# bat_connectors.net
KiCad netlist of a schematic drawn in Altium Designer
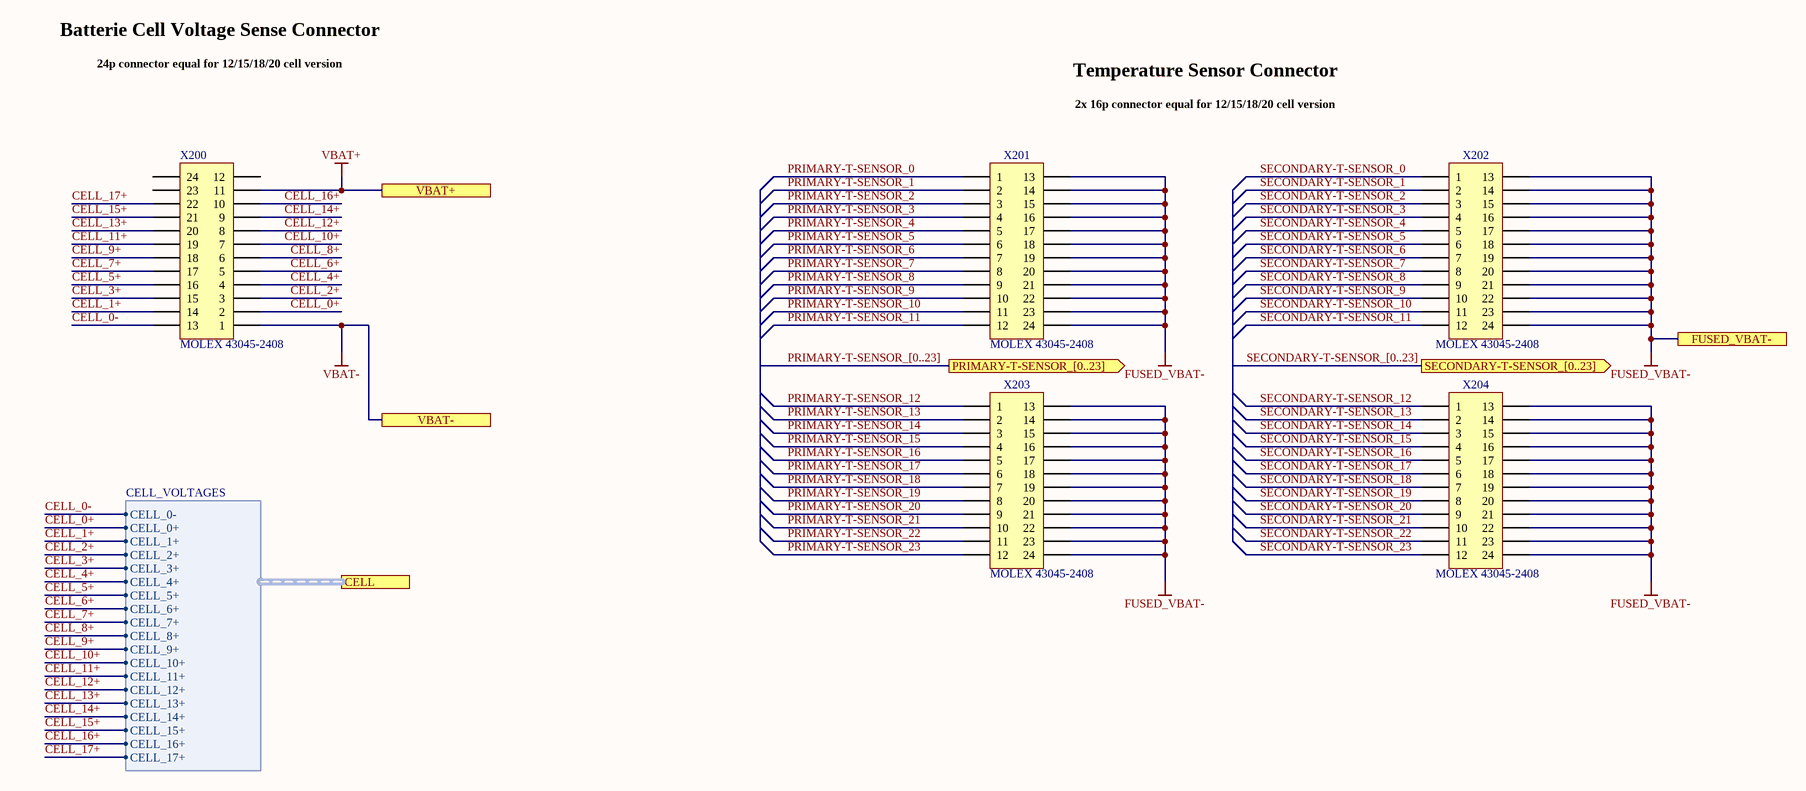
[diagram p0: bat_connectors.SchDoc]

(export (version "E")
  (design (tool "Eeschema 10.0.6"))
  (components
    (comp (ref "X200")
      (value "MOLEX 43045-2408")
      (footprint "MOLEX 43045-2408")
      (description "Micro-Fit 3.0 Right-Angle Header, 3.00mm Pitch, Dual Row, 24 Circuits")
      (libsource (lib "") (part "MOLEX 43045-2408_1"))
    )
    (comp (ref "X201")
      (value "MOLEX 43045-2408")
      (footprint "MOLEX 43045-2408")
      (description "Micro-Fit 3.0 Right-Angle Header, 3.00mm Pitch, Dual Row, 24 Circuits")
      (libsource (lib "Connector") (part "MOLEX 43045-2408"))
    )
    (comp (ref "X202")
      (value "MOLEX 43045-2408")
      (footprint "MOLEX 43045-2408")
      (description "Micro-Fit 3.0 Right-Angle Header, 3.00mm Pitch, Dual Row, 24 Circuits")
      (libsource (lib "Connector") (part "MOLEX 43045-2408"))
    )
    (comp (ref "X203")
      (value "MOLEX 43045-2408")
      (footprint "MOLEX 43045-2408")
      (description "Micro-Fit 3.0 Right-Angle Header, 3.00mm Pitch, Dual Row, 24 Circuits")
      (libsource (lib "Connector") (part "MOLEX 43045-2408"))
    )
    (comp (ref "X204")
      (value "MOLEX 43045-2408")
      (footprint "MOLEX 43045-2408")
      (description "Micro-Fit 3.0 Right-Angle Header, 3.00mm Pitch, Dual Row, 24 Circuits")
      (libsource (lib "Connector") (part "MOLEX 43045-2408"))
    )
  )
  (nets
    (net (code "2") (name "/CELL_0+") (class "Default")
      (node (ref "X200") (pin "2") (pinfunction "2_2") (pintype "passive"))
    )
    (net (code "3") (name "/CELL_0-") (class "Default")
      (node (ref "X200") (pin "13") (pinfunction "13_13") (pintype "passive"))
    )
    (net (code "4") (name "/CELL_1+") (class "Default")
      (node (ref "X200") (pin "14") (pinfunction "14_14") (pintype "passive"))
    )
    (net (code "5") (name "/CELL_2+") (class "Default")
      (node (ref "X200") (pin "3") (pinfunction "3_3") (pintype "passive"))
    )
    (net (code "6") (name "/CELL_3+") (class "Default")
      (node (ref "X200") (pin "15") (pinfunction "15_15") (pintype "passive"))
    )
    (net (code "7") (name "/CELL_4+") (class "Default")
      (node (ref "X200") (pin "4") (pinfunction "4_4") (pintype "passive"))
    )
    (net (code "8") (name "/CELL_5+") (class "Default")
      (node (ref "X200") (pin "16") (pinfunction "16_16") (pintype "passive"))
    )
    (net (code "9") (name "/CELL_6+") (class "Default")
      (node (ref "X200") (pin "5") (pinfunction "5_5") (pintype "passive"))
    )
    (net (code "10") (name "/CELL_7+") (class "Default")
      (node (ref "X200") (pin "17") (pinfunction "17_17") (pintype "passive"))
    )
    (net (code "11") (name "/CELL_8+") (class "Default")
      (node (ref "X200") (pin "6") (pinfunction "6_6") (pintype "passive"))
    )
    (net (code "12") (name "/CELL_9+") (class "Default")
      (node (ref "X200") (pin "18") (pinfunction "18_18") (pintype "passive"))
    )
    (net (code "13") (name "/CELL_10+") (class "Default")
      (node (ref "X200") (pin "7") (pinfunction "7_7") (pintype "passive"))
    )
    (net (code "14") (name "/CELL_11+") (class "Default")
      (node (ref "X200") (pin "19") (pinfunction "19_19") (pintype "passive"))
    )
    (net (code "15") (name "/CELL_12+") (class "Default")
      (node (ref "X200") (pin "8") (pinfunction "8_8") (pintype "passive"))
    )
    (net (code "16") (name "/CELL_13+") (class "Default")
      (node (ref "X200") (pin "20") (pinfunction "20_20") (pintype "passive"))
    )
    (net (code "17") (name "/CELL_14+") (class "Default")
      (node (ref "X200") (pin "9") (pinfunction "9_9") (pintype "passive"))
    )
    (net (code "18") (name "/CELL_15+") (class "Default")
      (node (ref "X200") (pin "21") (pinfunction "21_21") (pintype "passive"))
    )
    (net (code "19") (name "/CELL_16+") (class "Default")
      (node (ref "X200") (pin "10") (pinfunction "10_10") (pintype "passive"))
    )
    (net (code "20") (name "/CELL_17+") (class "Default")
      (node (ref "X200") (pin "22") (pinfunction "22_22") (pintype "passive"))
    )
    (net (code "21") (name "/PRIMARY-T-SENSOR_0") (class "Default")
      (node (ref "X201") (pin "1") (pinfunction "1_1") (pintype "passive"))
    )
    (net (code "22") (name "/PRIMARY-T-SENSOR_1") (class "Default")
      (node (ref "X201") (pin "2") (pinfunction "2_2") (pintype "passive"))
    )
    (net (code "23") (name "/PRIMARY-T-SENSOR_2") (class "Default")
      (node (ref "X201") (pin "3") (pinfunction "3_3") (pintype "passive"))
    )
    (net (code "24") (name "/PRIMARY-T-SENSOR_3") (class "Default")
      (node (ref "X201") (pin "4") (pinfunction "4_4") (pintype "passive"))
    )
    (net (code "25") (name "/PRIMARY-T-SENSOR_4") (class "Default")
      (node (ref "X201") (pin "5") (pinfunction "5_5") (pintype "passive"))
    )
    (net (code "26") (name "/PRIMARY-T-SENSOR_5") (class "Default")
      (node (ref "X201") (pin "6") (pinfunction "6_6") (pintype "passive"))
    )
    (net (code "27") (name "/PRIMARY-T-SENSOR_6") (class "Default")
      (node (ref "X201") (pin "7") (pinfunction "7_7") (pintype "passive"))
    )
    (net (code "28") (name "/PRIMARY-T-SENSOR_7") (class "Default")
      (node (ref "X201") (pin "8") (pinfunction "8_8") (pintype "passive"))
    )
    (net (code "29") (name "/PRIMARY-T-SENSOR_8") (class "Default")
      (node (ref "X201") (pin "9") (pinfunction "9_9") (pintype "passive"))
    )
    (net (code "30") (name "/PRIMARY-T-SENSOR_9") (class "Default")
      (node (ref "X201") (pin "10") (pinfunction "10_10") (pintype "passive"))
    )
    (net (code "31") (name "/PRIMARY-T-SENSOR_10") (class "Default")
      (node (ref "X201") (pin "11") (pinfunction "11_11") (pintype "passive"))
    )
    (net (code "32") (name "/PRIMARY-T-SENSOR_11") (class "Default")
      (node (ref "X201") (pin "12") (pinfunction "12_12") (pintype "passive"))
    )
    (net (code "33") (name "/PRIMARY-T-SENSOR_12") (class "Default")
      (node (ref "X203") (pin "1") (pinfunction "1_1") (pintype "passive"))
    )
    (net (code "34") (name "/PRIMARY-T-SENSOR_13") (class "Default")
      (node (ref "X203") (pin "2") (pinfunction "2_2") (pintype "passive"))
    )
    (net (code "35") (name "/PRIMARY-T-SENSOR_14") (class "Default")
      (node (ref "X203") (pin "3") (pinfunction "3_3") (pintype "passive"))
    )
    (net (code "36") (name "/PRIMARY-T-SENSOR_15") (class "Default")
      (node (ref "X203") (pin "4") (pinfunction "4_4") (pintype "passive"))
    )
    (net (code "37") (name "/PRIMARY-T-SENSOR_16") (class "Default")
      (node (ref "X203") (pin "5") (pinfunction "5_5") (pintype "passive"))
    )
    (net (code "38") (name "/PRIMARY-T-SENSOR_17") (class "Default")
      (node (ref "X203") (pin "6") (pinfunction "6_6") (pintype "passive"))
    )
    (net (code "39") (name "/PRIMARY-T-SENSOR_18") (class "Default")
      (node (ref "X203") (pin "7") (pinfunction "7_7") (pintype "passive"))
    )
    (net (code "40") (name "/PRIMARY-T-SENSOR_19") (class "Default")
      (node (ref "X203") (pin "8") (pinfunction "8_8") (pintype "passive"))
    )
    (net (code "41") (name "/PRIMARY-T-SENSOR_20") (class "Default")
      (node (ref "X203") (pin "9") (pinfunction "9_9") (pintype "passive"))
    )
    (net (code "42") (name "/PRIMARY-T-SENSOR_21") (class "Default")
      (node (ref "X203") (pin "10") (pinfunction "10_10") (pintype "passive"))
    )
    (net (code "43") (name "/PRIMARY-T-SENSOR_22") (class "Default")
      (node (ref "X203") (pin "11") (pinfunction "11_11") (pintype "passive"))
    )
    (net (code "44") (name "/PRIMARY-T-SENSOR_23") (class "Default")
      (node (ref "X203") (pin "12") (pinfunction "12_12") (pintype "passive"))
    )
    (net (code "46") (name "/SECONDARY-T-SENSOR_0") (class "Default")
      (node (ref "X202") (pin "1") (pinfunction "1_1") (pintype "passive"))
    )
    (net (code "47") (name "/SECONDARY-T-SENSOR_1") (class "Default")
      (node (ref "X202") (pin "2") (pinfunction "2_2") (pintype "passive"))
    )
    (net (code "48") (name "/SECONDARY-T-SENSOR_2") (class "Default")
      (node (ref "X202") (pin "3") (pinfunction "3_3") (pintype "passive"))
    )
    (net (code "49") (name "/SECONDARY-T-SENSOR_3") (class "Default")
      (node (ref "X202") (pin "4") (pinfunction "4_4") (pintype "passive"))
    )
    (net (code "50") (name "/SECONDARY-T-SENSOR_4") (class "Default")
      (node (ref "X202") (pin "5") (pinfunction "5_5") (pintype "passive"))
    )
    (net (code "51") (name "/SECONDARY-T-SENSOR_5") (class "Default")
      (node (ref "X202") (pin "6") (pinfunction "6_6") (pintype "passive"))
    )
    (net (code "52") (name "/SECONDARY-T-SENSOR_6") (class "Default")
      (node (ref "X202") (pin "7") (pinfunction "7_7") (pintype "passive"))
    )
    (net (code "53") (name "/SECONDARY-T-SENSOR_7") (class "Default")
      (node (ref "X202") (pin "8") (pinfunction "8_8") (pintype "passive"))
    )
    (net (code "54") (name "/SECONDARY-T-SENSOR_8") (class "Default")
      (node (ref "X202") (pin "9") (pinfunction "9_9") (pintype "passive"))
    )
    (net (code "55") (name "/SECONDARY-T-SENSOR_9") (class "Default")
      (node (ref "X202") (pin "10") (pinfunction "10_10") (pintype "passive"))
    )
    (net (code "56") (name "/SECONDARY-T-SENSOR_10") (class "Default")
      (node (ref "X202") (pin "11") (pinfunction "11_11") (pintype "passive"))
    )
    (net (code "57") (name "/SECONDARY-T-SENSOR_11") (class "Default")
      (node (ref "X202") (pin "12") (pinfunction "12_12") (pintype "passive"))
    )
    (net (code "58") (name "/SECONDARY-T-SENSOR_12") (class "Default")
      (node (ref "X204") (pin "1") (pinfunction "1_1") (pintype "passive"))
    )
    (net (code "59") (name "/SECONDARY-T-SENSOR_13") (class "Default")
      (node (ref "X204") (pin "2") (pinfunction "2_2") (pintype "passive"))
    )
    (net (code "60") (name "/SECONDARY-T-SENSOR_14") (class "Default")
      (node (ref "X204") (pin "3") (pinfunction "3_3") (pintype "passive"))
    )
    (net (code "61") (name "/SECONDARY-T-SENSOR_15") (class "Default")
      (node (ref "X204") (pin "4") (pinfunction "4_4") (pintype "passive"))
    )
    (net (code "62") (name "/SECONDARY-T-SENSOR_16") (class "Default")
      (node (ref "X204") (pin "5") (pinfunction "5_5") (pintype "passive"))
    )
    (net (code "63") (name "/SECONDARY-T-SENSOR_17") (class "Default")
      (node (ref "X204") (pin "6") (pinfunction "6_6") (pintype "passive"))
    )
    (net (code "64") (name "/SECONDARY-T-SENSOR_18") (class "Default")
      (node (ref "X204") (pin "7") (pinfunction "7_7") (pintype "passive"))
    )
    (net (code "65") (name "/SECONDARY-T-SENSOR_19") (class "Default")
      (node (ref "X204") (pin "8") (pinfunction "8_8") (pintype "passive"))
    )
    (net (code "66") (name "/SECONDARY-T-SENSOR_20") (class "Default")
      (node (ref "X204") (pin "9") (pinfunction "9_9") (pintype "passive"))
    )
    (net (code "67") (name "/SECONDARY-T-SENSOR_21") (class "Default")
      (node (ref "X204") (pin "10") (pinfunction "10_10") (pintype "passive"))
    )
    (net (code "68") (name "/SECONDARY-T-SENSOR_22") (class "Default")
      (node (ref "X204") (pin "11") (pinfunction "11_11") (pintype "passive"))
    )
    (net (code "69") (name "/SECONDARY-T-SENSOR_23") (class "Default")
      (node (ref "X204") (pin "12") (pinfunction "12_12") (pintype "passive"))
    )
    (net (code "72") (name "FUSED_VBAT-") (class "Default")
      (node (ref "X201") (pin "13") (pinfunction "13_13") (pintype "passive"))
      (node (ref "X201") (pin "14") (pinfunction "14_14") (pintype "passive"))
      (node (ref "X201") (pin "15") (pinfunction "15_15") (pintype "passive"))
      (node (ref "X201") (pin "16") (pinfunction "16_16") (pintype "passive"))
      (node (ref "X201") (pin "17") (pinfunction "17_17") (pintype "passive"))
      (node (ref "X201") (pin "18") (pinfunction "18_18") (pintype "passive"))
      (node (ref "X201") (pin "19") (pinfunction "19_19") (pintype "passive"))
      (node (ref "X201") (pin "20") (pinfunction "20_20") (pintype "passive"))
      (node (ref "X201") (pin "21") (pinfunction "21_21") (pintype "passive"))
      (node (ref "X201") (pin "22") (pinfunction "22_22") (pintype "passive"))
      (node (ref "X201") (pin "23") (pinfunction "23_23") (pintype "passive"))
      (node (ref "X201") (pin "24") (pinfunction "24_24") (pintype "passive"))
      (node (ref "X202") (pin "13") (pinfunction "13_13") (pintype "passive"))
      (node (ref "X202") (pin "14") (pinfunction "14_14") (pintype "passive"))
      (node (ref "X202") (pin "15") (pinfunction "15_15") (pintype "passive"))
      (node (ref "X202") (pin "16") (pinfunction "16_16") (pintype "passive"))
      (node (ref "X202") (pin "17") (pinfunction "17_17") (pintype "passive"))
      (node (ref "X202") (pin "18") (pinfunction "18_18") (pintype "passive"))
      (node (ref "X202") (pin "19") (pinfunction "19_19") (pintype "passive"))
      (node (ref "X202") (pin "20") (pinfunction "20_20") (pintype "passive"))
      (node (ref "X202") (pin "21") (pinfunction "21_21") (pintype "passive"))
      (node (ref "X202") (pin "22") (pinfunction "22_22") (pintype "passive"))
      (node (ref "X202") (pin "23") (pinfunction "23_23") (pintype "passive"))
      (node (ref "X202") (pin "24") (pinfunction "24_24") (pintype "passive"))
      (node (ref "X203") (pin "13") (pinfunction "13_13") (pintype "passive"))
      (node (ref "X203") (pin "14") (pinfunction "14_14") (pintype "passive"))
      (node (ref "X203") (pin "15") (pinfunction "15_15") (pintype "passive"))
      (node (ref "X203") (pin "16") (pinfunction "16_16") (pintype "passive"))
      (node (ref "X203") (pin "17") (pinfunction "17_17") (pintype "passive"))
      (node (ref "X203") (pin "18") (pinfunction "18_18") (pintype "passive"))
      (node (ref "X203") (pin "19") (pinfunction "19_19") (pintype "passive"))
      (node (ref "X203") (pin "20") (pinfunction "20_20") (pintype "passive"))
      (node (ref "X203") (pin "21") (pinfunction "21_21") (pintype "passive"))
      (node (ref "X203") (pin "22") (pinfunction "22_22") (pintype "passive"))
      (node (ref "X203") (pin "23") (pinfunction "23_23") (pintype "passive"))
      (node (ref "X203") (pin "24") (pinfunction "24_24") (pintype "passive"))
      (node (ref "X204") (pin "13") (pinfunction "13_13") (pintype "passive"))
      (node (ref "X204") (pin "14") (pinfunction "14_14") (pintype "passive"))
      (node (ref "X204") (pin "15") (pinfunction "15_15") (pintype "passive"))
      (node (ref "X204") (pin "16") (pinfunction "16_16") (pintype "passive"))
      (node (ref "X204") (pin "17") (pinfunction "17_17") (pintype "passive"))
      (node (ref "X204") (pin "18") (pinfunction "18_18") (pintype "passive"))
      (node (ref "X204") (pin "19") (pinfunction "19_19") (pintype "passive"))
      (node (ref "X204") (pin "20") (pinfunction "20_20") (pintype "passive"))
      (node (ref "X204") (pin "21") (pinfunction "21_21") (pintype "passive"))
      (node (ref "X204") (pin "22") (pinfunction "22_22") (pintype "passive"))
      (node (ref "X204") (pin "23") (pinfunction "23_23") (pintype "passive"))
      (node (ref "X204") (pin "24") (pinfunction "24_24") (pintype "passive"))
    )
    (net (code "73") (name "VBAT+") (class "Default")
      (node (ref "X200") (pin "11") (pinfunction "11_11") (pintype "passive"))
    )
    (net (code "74") (name "VBAT-") (class "Default")
      (node (ref "X200") (pin "1") (pinfunction "1_1") (pintype "passive"))
    )
    (net (code "75") (name "unconnected-(X200-Pad12)") (class "Default")
      (node (ref "X200") (pin "12") (pinfunction "12_12") (pintype "passive"))
    )
    (net (code "76") (name "unconnected-(X200-Pad23)") (class "Default")
      (node (ref "X200") (pin "23") (pinfunction "23_23") (pintype "passive"))
    )
    (net (code "77") (name "unconnected-(X200-Pad24)") (class "Default")
      (node (ref "X200") (pin "24") (pinfunction "24_24") (pintype "passive"))
    )
  )
)
